# 16-FPGA-02a.net
KiCad netlist of a schematic drawn in Altium Designer
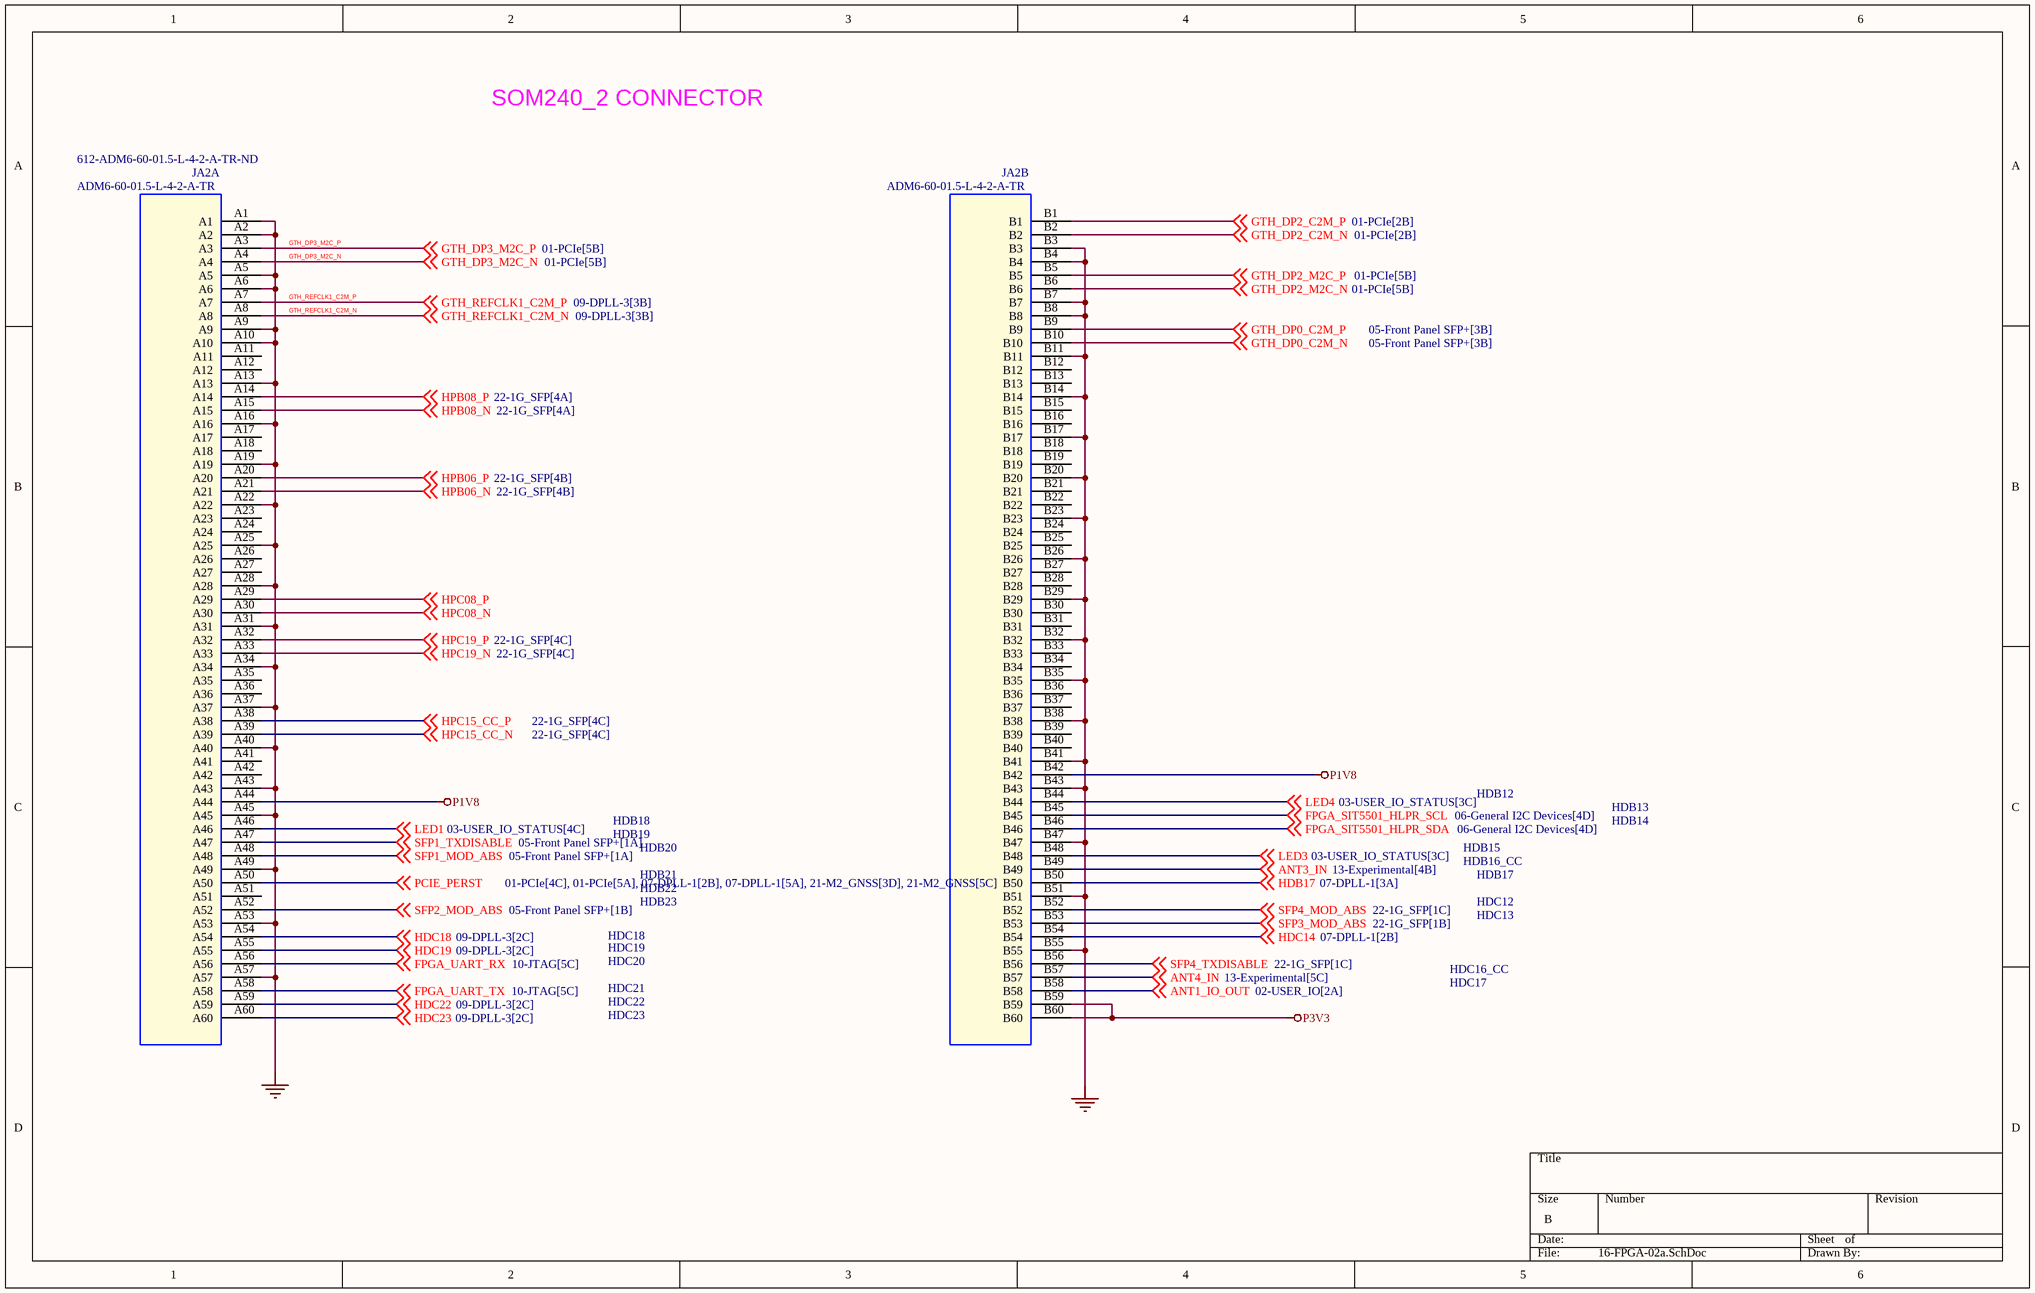
[diagram p0: 16-FPGA-02a.SchDoc]

(export (version "E")
  (design (tool "Eeschema 10.0.6"))
  (components
    (comp (ref "JA2")
      (value "ADM6-60-01.5-L-4-2-A-TR")
      (footprint "CON_SAMTEC_ADM6_60_4")
      (description "Conn Rcpt Male Vert 240 Pos 4x60 0.635mm P Black SMT")
      (fields
        (field (name "MANUFACTURER") "Samtec Inc.")
        (field (name "AGILE PART NUMBER") "CON-00383-01")
        (field (name "SUPPLIER PART NUMBER 1") "612-ADM6-60-01.5-L-4-2-A-TR-ND")
      )
      (libsource (lib "*") (part "SAMTEC-ADx6-60X4"))
    )
  )
  (nets
    (net (code "1") (name "ANT1_IO_OUT") (class "Default")
      (node (ref "JA2") (pin "B58") (pinfunction "B58_B58") (pintype "passive"))
    )
    (net (code "2") (name "ANT3_IN") (class "Default")
      (node (ref "JA2") (pin "B49") (pinfunction "B49_B49") (pintype "passive"))
    )
    (net (code "3") (name "ANT4_IN") (class "Default")
      (node (ref "JA2") (pin "B57") (pinfunction "B57_B57") (pintype "passive"))
    )
    (net (code "4") (name "FPGA_SIT5501_HLPR_SCL") (class "Default")
      (node (ref "JA2") (pin "B45") (pinfunction "B45_B45") (pintype "passive"))
    )
    (net (code "5") (name "FPGA_SIT5501_HLPR_SDA") (class "Default")
      (node (ref "JA2") (pin "B46") (pinfunction "B46_B46") (pintype "passive"))
    )
    (net (code "6") (name "FPGA_UART_RX") (class "Default")
      (node (ref "JA2") (pin "A56") (pinfunction "A56_A56") (pintype "passive"))
    )
    (net (code "7") (name "FPGA_UART_TX") (class "Default")
      (node (ref "JA2") (pin "A58") (pinfunction "A58_A58") (pintype "passive"))
    )
    (net (code "8") (name "GND") (class "Default")
      (node (ref "JA2") (pin "A1") (pinfunction "A1_A1") (pintype "passive"))
      (node (ref "JA2") (pin "A10") (pinfunction "A10_A10") (pintype "passive"))
      (node (ref "JA2") (pin "A13") (pinfunction "A13_A13") (pintype "passive"))
      (node (ref "JA2") (pin "A16") (pinfunction "A16_A16") (pintype "passive"))
      (node (ref "JA2") (pin "A19") (pinfunction "A19_A19") (pintype "passive"))
      (node (ref "JA2") (pin "A2") (pinfunction "A2_A2") (pintype "passive"))
      (node (ref "JA2") (pin "A22") (pinfunction "A22_A22") (pintype "passive"))
      (node (ref "JA2") (pin "A25") (pinfunction "A25_A25") (pintype "passive"))
      (node (ref "JA2") (pin "A28") (pinfunction "A28_A28") (pintype "passive"))
      (node (ref "JA2") (pin "A31") (pinfunction "A31_A31") (pintype "passive"))
      (node (ref "JA2") (pin "A34") (pinfunction "A34_A34") (pintype "passive"))
      (node (ref "JA2") (pin "A37") (pinfunction "A37_A37") (pintype "passive"))
      (node (ref "JA2") (pin "A40") (pinfunction "A40_A40") (pintype "passive"))
      (node (ref "JA2") (pin "A43") (pinfunction "A43_A43") (pintype "passive"))
      (node (ref "JA2") (pin "A45") (pinfunction "A45_A45") (pintype "passive"))
      (node (ref "JA2") (pin "A49") (pinfunction "A49_A49") (pintype "passive"))
      (node (ref "JA2") (pin "A5") (pinfunction "A5_A5") (pintype "passive"))
      (node (ref "JA2") (pin "A53") (pinfunction "A53_A53") (pintype "passive"))
      (node (ref "JA2") (pin "A57") (pinfunction "A57_A57") (pintype "passive"))
      (node (ref "JA2") (pin "A6") (pinfunction "A6_A6") (pintype "passive"))
      (node (ref "JA2") (pin "A9") (pinfunction "A9_A9") (pintype "passive"))
      (node (ref "JA2") (pin "B11") (pinfunction "B11_B11") (pintype "passive"))
      (node (ref "JA2") (pin "B14") (pinfunction "B14_B14") (pintype "passive"))
      (node (ref "JA2") (pin "B17") (pinfunction "B17_B17") (pintype "passive"))
      (node (ref "JA2") (pin "B20") (pinfunction "B20_B20") (pintype "passive"))
      (node (ref "JA2") (pin "B23") (pinfunction "B23_B23") (pintype "passive"))
      (node (ref "JA2") (pin "B26") (pinfunction "B26_B26") (pintype "passive"))
      (node (ref "JA2") (pin "B29") (pinfunction "B29_B29") (pintype "passive"))
      (node (ref "JA2") (pin "B3") (pinfunction "B3_B3") (pintype "passive"))
      (node (ref "JA2") (pin "B32") (pinfunction "B32_B32") (pintype "passive"))
      (node (ref "JA2") (pin "B35") (pinfunction "B35_B35") (pintype "passive"))
      (node (ref "JA2") (pin "B38") (pinfunction "B38_B38") (pintype "passive"))
      (node (ref "JA2") (pin "B4") (pinfunction "B4_B4") (pintype "passive"))
      (node (ref "JA2") (pin "B41") (pinfunction "B41_B41") (pintype "passive"))
      (node (ref "JA2") (pin "B43") (pinfunction "B43_B43") (pintype "passive"))
      (node (ref "JA2") (pin "B47") (pinfunction "B47_B47") (pintype "passive"))
      (node (ref "JA2") (pin "B51") (pinfunction "B51_B51") (pintype "passive"))
      (node (ref "JA2") (pin "B55") (pinfunction "B55_B55") (pintype "passive"))
      (node (ref "JA2") (pin "B7") (pinfunction "B7_B7") (pintype "passive"))
      (node (ref "JA2") (pin "B8") (pinfunction "B8_B8") (pintype "passive"))
    )
    (net (code "9") (name "GTH_DP0_C2M_N") (class "Default")
      (node (ref "JA2") (pin "B10") (pinfunction "B10_B10") (pintype "passive"))
    )
    (net (code "10") (name "GTH_DP0_C2M_P") (class "Default")
      (node (ref "JA2") (pin "B9") (pinfunction "B9_B9") (pintype "passive"))
    )
    (net (code "11") (name "GTH_DP2_C2M_N") (class "Default")
      (node (ref "JA2") (pin "B2") (pinfunction "B2_B2") (pintype "passive"))
    )
    (net (code "12") (name "GTH_DP2_C2M_P") (class "Default")
      (node (ref "JA2") (pin "B1") (pinfunction "B1_B1") (pintype "passive"))
    )
    (net (code "13") (name "GTH_DP2_M2C_N") (class "Default")
      (node (ref "JA2") (pin "B6") (pinfunction "B6_B6") (pintype "passive"))
    )
    (net (code "14") (name "GTH_DP2_M2C_P") (class "Default")
      (node (ref "JA2") (pin "B5") (pinfunction "B5_B5") (pintype "passive"))
    )
    (net (code "15") (name "GTH_DP3_M2C_N") (class "Default")
      (node (ref "JA2") (pin "A4") (pinfunction "A4_A4") (pintype "passive"))
    )
    (net (code "16") (name "GTH_DP3_M2C_P") (class "Default")
      (node (ref "JA2") (pin "A3") (pinfunction "A3_A3") (pintype "passive"))
    )
    (net (code "17") (name "GTH_REFCLK1_C2M_N") (class "Default")
      (node (ref "JA2") (pin "A8") (pinfunction "A8_A8") (pintype "passive"))
    )
    (net (code "18") (name "GTH_REFCLK1_C2M_P") (class "Default")
      (node (ref "JA2") (pin "A7") (pinfunction "A7_A7") (pintype "passive"))
    )
    (net (code "19") (name "HDB17") (class "Default")
      (node (ref "JA2") (pin "B50") (pinfunction "B50_B50") (pintype "passive"))
    )
    (net (code "20") (name "HDC14") (class "Default")
      (node (ref "JA2") (pin "B54") (pinfunction "B54_B54") (pintype "passive"))
    )
    (net (code "21") (name "HDC18") (class "Default")
      (node (ref "JA2") (pin "A54") (pinfunction "A54_A54") (pintype "passive"))
    )
    (net (code "22") (name "HDC19") (class "Default")
      (node (ref "JA2") (pin "A55") (pinfunction "A55_A55") (pintype "passive"))
    )
    (net (code "23") (name "HDC22") (class "Default")
      (node (ref "JA2") (pin "A59") (pinfunction "A59_A59") (pintype "passive"))
    )
    (net (code "24") (name "HDC23") (class "Default")
      (node (ref "JA2") (pin "A60") (pinfunction "A60_A60") (pintype "passive"))
    )
    (net (code "25") (name "HPB06_N") (class "Default")
      (node (ref "JA2") (pin "A21") (pinfunction "A21_A21") (pintype "passive"))
    )
    (net (code "26") (name "HPB06_P") (class "Default")
      (node (ref "JA2") (pin "A20") (pinfunction "A20_A20") (pintype "passive"))
    )
    (net (code "27") (name "HPB08_N") (class "Default")
      (node (ref "JA2") (pin "A15") (pinfunction "A15_A15") (pintype "passive"))
    )
    (net (code "28") (name "HPB08_P") (class "Default")
      (node (ref "JA2") (pin "A14") (pinfunction "A14_A14") (pintype "passive"))
    )
    (net (code "29") (name "HPC08_N") (class "Default")
      (node (ref "JA2") (pin "A30") (pinfunction "A30_A30") (pintype "passive"))
    )
    (net (code "30") (name "HPC08_P") (class "Default")
      (node (ref "JA2") (pin "A29") (pinfunction "A29_A29") (pintype "passive"))
    )
    (net (code "31") (name "HPC15_CC_N") (class "Default")
      (node (ref "JA2") (pin "A39") (pinfunction "A39_A39") (pintype "passive"))
    )
    (net (code "32") (name "HPC15_CC_P") (class "Default")
      (node (ref "JA2") (pin "A38") (pinfunction "A38_A38") (pintype "passive"))
    )
    (net (code "33") (name "HPC19_N") (class "Default")
      (node (ref "JA2") (pin "A33") (pinfunction "A33_A33") (pintype "passive"))
    )
    (net (code "34") (name "HPC19_P") (class "Default")
      (node (ref "JA2") (pin "A32") (pinfunction "A32_A32") (pintype "passive"))
    )
    (net (code "35") (name "LED1") (class "Default")
      (node (ref "JA2") (pin "A46") (pinfunction "A46_A46") (pintype "passive"))
    )
    (net (code "36") (name "LED3") (class "Default")
      (node (ref "JA2") (pin "B48") (pinfunction "B48_B48") (pintype "passive"))
    )
    (net (code "37") (name "LED4") (class "Default")
      (node (ref "JA2") (pin "B44") (pinfunction "B44_B44") (pintype "passive"))
    )
    (net (code "38") (name "P1V8") (class "Default")
      (node (ref "JA2") (pin "A44") (pinfunction "A44_A44") (pintype "passive"))
      (node (ref "JA2") (pin "B42") (pinfunction "B42_B42") (pintype "passive"))
    )
    (net (code "39") (name "P3V3") (class "Default")
      (node (ref "JA2") (pin "B59") (pinfunction "B59_B59") (pintype "passive"))
      (node (ref "JA2") (pin "B60") (pinfunction "B60_B60") (pintype "passive"))
    )
    (net (code "40") (name "PCIE_PERST") (class "Default")
      (node (ref "JA2") (pin "A50") (pinfunction "A50_A50") (pintype "passive"))
    )
    (net (code "41") (name "SFP1_MOD_ABS") (class "Default")
      (node (ref "JA2") (pin "A48") (pinfunction "A48_A48") (pintype "passive"))
    )
    (net (code "42") (name "SFP1_TXDISABLE") (class "Default")
      (node (ref "JA2") (pin "A47") (pinfunction "A47_A47") (pintype "passive"))
    )
    (net (code "43") (name "SFP2_MOD_ABS") (class "Default")
      (node (ref "JA2") (pin "A52") (pinfunction "A52_A52") (pintype "passive"))
    )
    (net (code "44") (name "SFP3_MOD_ABS") (class "Default")
      (node (ref "JA2") (pin "B53") (pinfunction "B53_B53") (pintype "passive"))
    )
    (net (code "45") (name "SFP4_MOD_ABS") (class "Default")
      (node (ref "JA2") (pin "B52") (pinfunction "B52_B52") (pintype "passive"))
    )
    (net (code "46") (name "SFP4_TXDISABLE") (class "Default")
      (node (ref "JA2") (pin "B56") (pinfunction "B56_B56") (pintype "passive"))
    )
    (net (code "47") (name "unconnected-(JA2-PadA11)") (class "Default")
      (node (ref "JA2") (pin "A11") (pinfunction "A11_A11") (pintype "passive"))
    )
    (net (code "48") (name "unconnected-(JA2-PadA12)") (class "Default")
      (node (ref "JA2") (pin "A12") (pinfunction "A12_A12") (pintype "passive"))
    )
    (net (code "49") (name "unconnected-(JA2-PadA17)") (class "Default")
      (node (ref "JA2") (pin "A17") (pinfunction "A17_A17") (pintype "passive"))
    )
    (net (code "50") (name "unconnected-(JA2-PadA18)") (class "Default")
      (node (ref "JA2") (pin "A18") (pinfunction "A18_A18") (pintype "passive"))
    )
    (net (code "51") (name "unconnected-(JA2-PadA23)") (class "Default")
      (node (ref "JA2") (pin "A23") (pinfunction "A23_A23") (pintype "passive"))
    )
    (net (code "52") (name "unconnected-(JA2-PadA24)") (class "Default")
      (node (ref "JA2") (pin "A24") (pinfunction "A24_A24") (pintype "passive"))
    )
    (net (code "53") (name "unconnected-(JA2-PadA26)") (class "Default")
      (node (ref "JA2") (pin "A26") (pinfunction "A26_A26") (pintype "passive"))
    )
    (net (code "54") (name "unconnected-(JA2-PadA27)") (class "Default")
      (node (ref "JA2") (pin "A27") (pinfunction "A27_A27") (pintype "passive"))
    )
    (net (code "55") (name "unconnected-(JA2-PadA35)") (class "Default")
      (node (ref "JA2") (pin "A35") (pinfunction "A35_A35") (pintype "passive"))
    )
    (net (code "56") (name "unconnected-(JA2-PadA36)") (class "Default")
      (node (ref "JA2") (pin "A36") (pinfunction "A36_A36") (pintype "passive"))
    )
    (net (code "57") (name "unconnected-(JA2-PadA41)") (class "Default")
      (node (ref "JA2") (pin "A41") (pinfunction "A41_A41") (pintype "passive"))
    )
    (net (code "58") (name "unconnected-(JA2-PadA42)") (class "Default")
      (node (ref "JA2") (pin "A42") (pinfunction "A42_A42") (pintype "passive"))
    )
    (net (code "59") (name "unconnected-(JA2-PadA51)") (class "Default")
      (node (ref "JA2") (pin "A51") (pinfunction "A51_A51") (pintype "passive"))
    )
    (net (code "60") (name "unconnected-(JA2-PadB12)") (class "Default")
      (node (ref "JA2") (pin "B12") (pinfunction "B12_B12") (pintype "passive"))
    )
    (net (code "61") (name "unconnected-(JA2-PadB13)") (class "Default")
      (node (ref "JA2") (pin "B13") (pinfunction "B13_B13") (pintype "passive"))
    )
    (net (code "62") (name "unconnected-(JA2-PadB15)") (class "Default")
      (node (ref "JA2") (pin "B15") (pinfunction "B15_B15") (pintype "passive"))
    )
    (net (code "63") (name "unconnected-(JA2-PadB16)") (class "Default")
      (node (ref "JA2") (pin "B16") (pinfunction "B16_B16") (pintype "passive"))
    )
    (net (code "64") (name "unconnected-(JA2-PadB18)") (class "Default")
      (node (ref "JA2") (pin "B18") (pinfunction "B18_B18") (pintype "passive"))
    )
    (net (code "65") (name "unconnected-(JA2-PadB19)") (class "Default")
      (node (ref "JA2") (pin "B19") (pinfunction "B19_B19") (pintype "passive"))
    )
    (net (code "66") (name "unconnected-(JA2-PadB21)") (class "Default")
      (node (ref "JA2") (pin "B21") (pinfunction "B21_B21") (pintype "passive"))
    )
    (net (code "67") (name "unconnected-(JA2-PadB22)") (class "Default")
      (node (ref "JA2") (pin "B22") (pinfunction "B22_B22") (pintype "passive"))
    )
    (net (code "68") (name "unconnected-(JA2-PadB24)") (class "Default")
      (node (ref "JA2") (pin "B24") (pinfunction "B24_B24") (pintype "passive"))
    )
    (net (code "69") (name "unconnected-(JA2-PadB25)") (class "Default")
      (node (ref "JA2") (pin "B25") (pinfunction "B25_B25") (pintype "passive"))
    )
    (net (code "70") (name "unconnected-(JA2-PadB27)") (class "Default")
      (node (ref "JA2") (pin "B27") (pinfunction "B27_B27") (pintype "passive"))
    )
    (net (code "71") (name "unconnected-(JA2-PadB28)") (class "Default")
      (node (ref "JA2") (pin "B28") (pinfunction "B28_B28") (pintype "passive"))
    )
    (net (code "72") (name "unconnected-(JA2-PadB30)") (class "Default")
      (node (ref "JA2") (pin "B30") (pinfunction "B30_B30") (pintype "passive"))
    )
    (net (code "73") (name "unconnected-(JA2-PadB31)") (class "Default")
      (node (ref "JA2") (pin "B31") (pinfunction "B31_B31") (pintype "passive"))
    )
    (net (code "74") (name "unconnected-(JA2-PadB33)") (class "Default")
      (node (ref "JA2") (pin "B33") (pinfunction "B33_B33") (pintype "passive"))
    )
    (net (code "75") (name "unconnected-(JA2-PadB34)") (class "Default")
      (node (ref "JA2") (pin "B34") (pinfunction "B34_B34") (pintype "passive"))
    )
    (net (code "76") (name "unconnected-(JA2-PadB36)") (class "Default")
      (node (ref "JA2") (pin "B36") (pinfunction "B36_B36") (pintype "passive"))
    )
    (net (code "77") (name "unconnected-(JA2-PadB37)") (class "Default")
      (node (ref "JA2") (pin "B37") (pinfunction "B37_B37") (pintype "passive"))
    )
    (net (code "78") (name "unconnected-(JA2-PadB39)") (class "Default")
      (node (ref "JA2") (pin "B39") (pinfunction "B39_B39") (pintype "passive"))
    )
    (net (code "79") (name "unconnected-(JA2-PadB40)") (class "Default")
      (node (ref "JA2") (pin "B40") (pinfunction "B40_B40") (pintype "passive"))
    )
  )
)
